# 04-AT86RF215IQ.net
KiCad netlist of a schematic drawn in Altium Designer
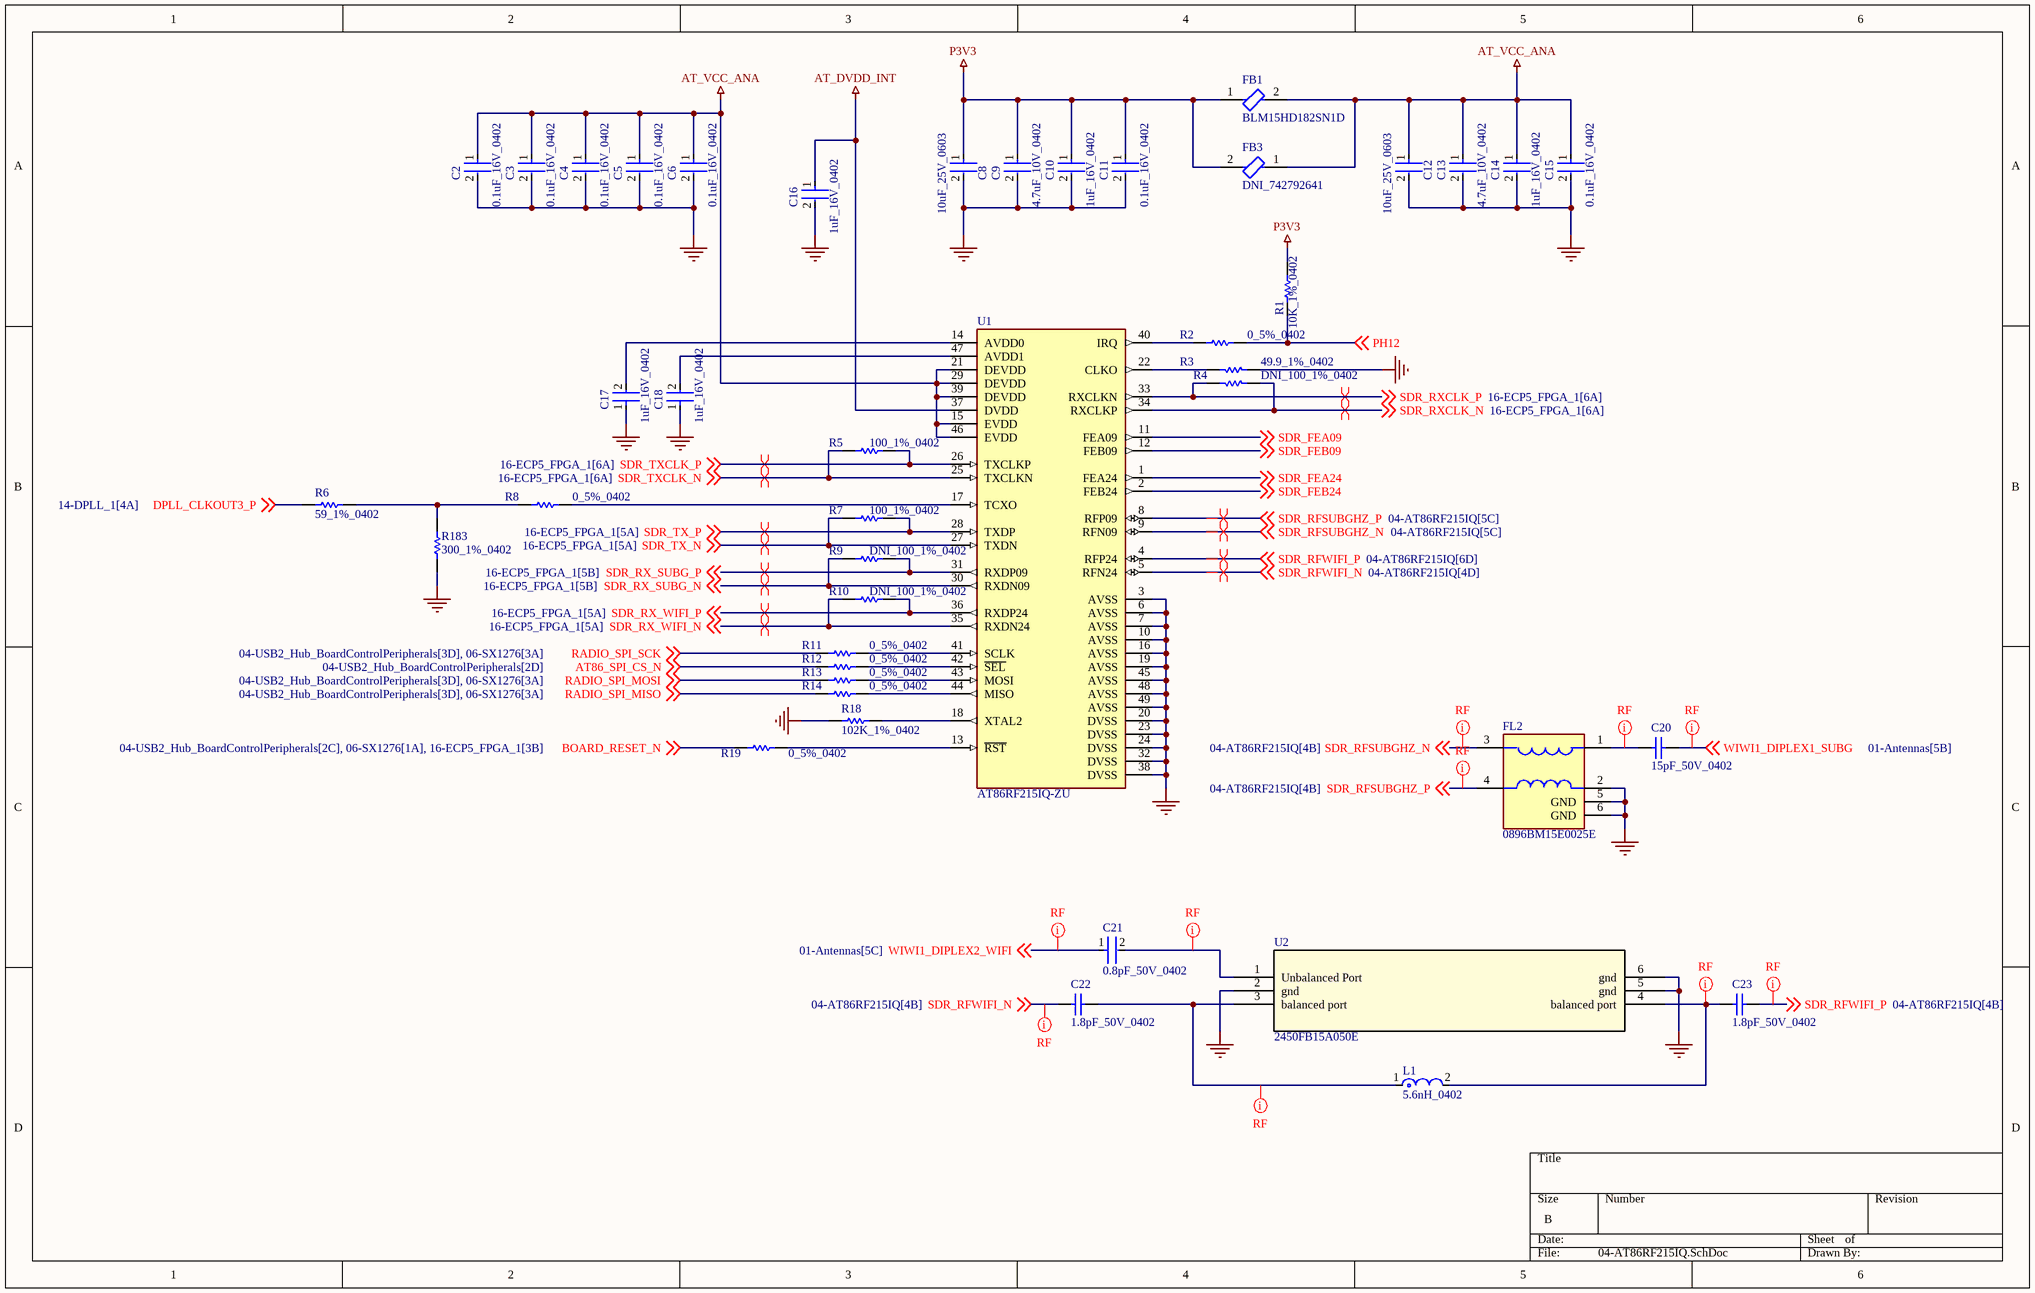
[diagram p0: 04-AT86RF215IQ.SchDoc]

(export (version "E")
  (design (tool "Eeschema 10.0.6"))
  (components
    (comp (ref "C2")
      (value "0.1uF_16V_0402")
      (footprint "FP-C0402-BB-MFG")
      (description "CAP CER 0.1UF 16V 5% X7R 0402")
      (fields
        (field (name "MANUFACTURER") "Kemet")
        (field (name "MANUFACTURER PART NUMBER") "C0402C104J4RACTU")
      )
      (libsource (lib "Altium Content Vault") (part "b4654b650e69147ec39a6b967a45e02"))
    )
    (comp (ref "C3")
      (value "0.1uF_16V_0402")
      (footprint "FP-C0402-BB-MFG")
      (description "CAP CER 0.1UF 16V 5% X7R 0402")
      (fields
        (field (name "MANUFACTURER") "Kemet")
        (field (name "MANUFACTURER PART NUMBER") "C0402C104J4RACTU")
      )
      (libsource (lib "Altium Content Vault") (part "b4654b650e69147ec39a6b967a45e02"))
    )
    (comp (ref "C4")
      (value "0.1uF_16V_0402")
      (footprint "FP-C0402-BB-MFG")
      (description "CAP CER 0.1UF 16V 5% X7R 0402")
      (fields
        (field (name "MANUFACTURER") "Kemet")
        (field (name "MANUFACTURER PART NUMBER") "C0402C104J4RACTU")
      )
      (libsource (lib "Altium Content Vault") (part "b4654b650e69147ec39a6b967a45e02"))
    )
    (comp (ref "C5")
      (value "0.1uF_16V_0402")
      (footprint "FP-C0402-BB-MFG")
      (description "CAP CER 0.1UF 16V 5% X7R 0402")
      (fields
        (field (name "MANUFACTURER") "Kemet")
        (field (name "MANUFACTURER PART NUMBER") "C0402C104J4RACTU")
      )
      (libsource (lib "Altium Content Vault") (part "b4654b650e69147ec39a6b967a45e02"))
    )
    (comp (ref "C6")
      (value "0.1uF_16V_0402")
      (footprint "FP-C0402-BB-MFG")
      (description "CAP CER 0.1UF 16V 5% X7R 0402")
      (fields
        (field (name "MANUFACTURER") "Kemet")
        (field (name "MANUFACTURER PART NUMBER") "C0402C104J4RACTU")
      )
      (libsource (lib "Altium Content Vault") (part "b4654b650e69147ec39a6b967a45e02"))
    )
    (comp (ref "C8")
      (value "10uF_25V_0603")
      (footprint "FP-CL10-IPC_C")
      (description "Cap Ceramic 10uF 25V X5R ±20% Pad SMD 0603 +85°C T/R")
      (fields (field (name "TOLERANCE") "20%"))
      (libsource (lib "Altium Content Vault") (part "b4654b650e69147ec39a6b967a45e02"))
    )
    (comp (ref "C9")
      (value "4.7uF_10V_0402")
      (footprint "FP-C1005-050-0_15-MFG")
      (description "CAP CER 4.7UF 10V X5R 0402")
      (fields (field (name "TOLERANCE") "10%"))
      (libsource (lib "Altium Content Vault") (part "b4654b650e69147ec39a6b967a45e02"))
    )
    (comp (ref "C10")
      (value "1uF_16V_0402")
      (footprint "FP-0402-L_1_0_0_05-W_0_5-IPC_A")
      (description "None")
      (fields (field (name "TOLERANCE") "10%"))
      (libsource (lib "Altium Content Vault") (part "b4654b650e69147ec39a6b967a45e02"))
    )
    (comp (ref "C11")
      (value "0.1uF_16V_0402")
      (footprint "FP-C0402-BB-MFG")
      (description "CAP CER 0.1UF 16V 5% X7R 0402")
      (fields
        (field (name "MANUFACTURER") "Kemet")
        (field (name "MANUFACTURER PART NUMBER") "C0402C104J4RACTU")
      )
      (libsource (lib "Altium Content Vault") (part "b4654b650e69147ec39a6b967a45e02"))
    )
    (comp (ref "C12")
      (value "10uF_25V_0603")
      (footprint "FP-CL10-IPC_C")
      (description "Cap Ceramic 10uF 25V X5R ±20% Pad SMD 0603 +85°C T/R")
      (fields (field (name "TOLERANCE") "20%"))
      (libsource (lib "Altium Content Vault") (part "b4654b650e69147ec39a6b967a45e02"))
    )
    (comp (ref "C13")
      (value "4.7uF_10V_0402")
      (footprint "FP-C1005-050-0_15-MFG")
      (description "CAP CER 4.7UF 10V X5R 0402")
      (fields (field (name "TOLERANCE") "10%"))
      (libsource (lib "Altium Content Vault") (part "b4654b650e69147ec39a6b967a45e02"))
    )
    (comp (ref "C14")
      (value "1uF_16V_0402")
      (footprint "FP-0402-L_1_0_0_05-W_0_5-IPC_A")
      (description "None")
      (fields (field (name "TOLERANCE") "10%"))
      (libsource (lib "Altium Content Vault") (part "b4654b650e69147ec39a6b967a45e02"))
    )
    (comp (ref "C15")
      (value "0.1uF_16V_0402")
      (footprint "FP-C0402-BB-MFG")
      (description "CAP CER 0.1UF 16V 5% X7R 0402")
      (fields
        (field (name "MANUFACTURER") "Kemet")
        (field (name "MANUFACTURER PART NUMBER") "C0402C104J4RACTU")
      )
      (libsource (lib "Altium Content Vault") (part "b4654b650e69147ec39a6b967a45e02"))
    )
    (comp (ref "C16")
      (value "1uF_16V_0402")
      (footprint "FP-0402-L_1_0_0_05-W_0_5-IPC_A")
      (description "None")
      (fields (field (name "TOLERANCE") "10%"))
      (libsource (lib "Altium Content Vault") (part "b4654b650e69147ec39a6b967a45e02"))
    )
    (comp (ref "C17")
      (value "1uF_16V_0402")
      (footprint "FP-0402-L_1_0_0_05-W_0_5-IPC_A")
      (description "None")
      (fields (field (name "TOLERANCE") "10%"))
      (libsource (lib "Altium Content Vault") (part "b4654b650e69147ec39a6b967a45e02"))
    )
    (comp (ref "C18")
      (value "1uF_16V_0402")
      (footprint "FP-0402-L_1_0_0_05-W_0_5-IPC_A")
      (description "None")
      (fields (field (name "TOLERANCE") "10%"))
      (libsource (lib "Altium Content Vault") (part "b4654b650e69147ec39a6b967a45e02"))
    )
    (comp (ref "C20")
      (value "15pF_50V_0402")
      (footprint "CAPC1005X55X25NL05T10")
      (fields (field (name "PART NUMBER") "GRM1555C1H150JZ01D") (field (name "MANUFACTURER") "Murata"))
      (libsource (lib "Altium Content Vault") (part "CAP"))
    )
    (comp (ref "C21")
      (value "0.8pF_50V_0402")
      (footprint "FP-GJM155-0_05-IPC_A")
      (description "Multi-Layer Ceramic Capacitor 0.8pF C0G  ±0.1pF 0402 Paper T/R")
      (fields (field (name "VOLTAGE") "50V"))
      (libsource (lib "Altium Content Vault") (part "02cd4be3c70576c341d710602a673aa"))
    )
    (comp (ref "C22")
      (value "1.8pF_50V_0402")
      (footprint "CAPC1005X55X25LL05T10")
      (fields (field (name "PART NUMBER") "GRM1555C1H1R8CA01D") (field (name "MANUFACTURER") "Murata"))
      (libsource (lib "Altium Content Vault") (part "CAP"))
    )
    (comp (ref "C23")
      (value "1.8pF_50V_0402")
      (footprint "CAPC1005X55X25LL05T10")
      (fields (field (name "PART NUMBER") "GRM1555C1H1R8CA01D") (field (name "MANUFACTURER") "Murata"))
      (libsource (lib "Altium Content Vault") (part "CAP"))
    )
    (comp (ref "FB1")
      (value "BLM15HD182SN1D")
      (footprint "FP-BLM15-0_05-MFG")
      (description "Chip Ferrite Bead, 0402, 1800Ω @ 100MHz, 2.2Ω, 25%, 200mA")
      (fields (field (name "TOLERANCE") "25%"))
      (libsource (lib "Altium Content Vault") (part "5f30dd21d616792df468990f7003faa"))
    )
    (comp (ref "FB3")
      (value "DNI_742792641")
      (footprint "FP-742792641-MFG")
      (description "FERRITE BEAD 300 OHM 0603 1LN")
      (fields (field (name "TOLERANCE") "25%"))
      (libsource (lib "Altium Content Vault") (part "5f30dd21d616792df468990f7003faa"))
    )
    (comp (ref "FL2")
      (value "0896BM15E0025E")
      (footprint "FP-0896BM15E0025E-MFG")
      (description "BALUN 863MHZ-928MHZ 50/50 0805")
      (fields
        (field (name "MANUFACTURER") "Johanson")
        (field (name "OCTOPART") "https://octopart.com/0896bm15e0025e-johanson-71691697")
      )
      (libsource (lib "Altium Content Vault") (part "9725e6fc3b6d4b71249fb6cd7b91a1d"))
    )
    (comp (ref "L1")
      (value "5.6nH_0402")
      (footprint "FP-LQG15HH_02-IPC_A")
      (description "Multilayer type RF Inductor 5.6nH ±0.3nH 0.18Ω 600mA 0402")
      (libsource (lib "Altium Content Vault") (part "4cc4b267dca4c8e51f7102f422741d8"))
    )
    (comp (ref "R1")
      (value "10K_1%_0402")
      (footprint "RESC1005X40X25NL10T10")
      (fields (field (name "MANUFACTURER") "Bourns") (field (name "PART NUMBER") "CR0402-FX-1002GLF"))
      (libsource (lib "Altium Content Vault") (part "RES"))
    )
    (comp (ref "R2")
      (value "0_5%_0402")
      (footprint "RESC1005X40X25NL05T10")
      (fields (field (name "MANUFACTURER") "Panasonic") (field (name "PART NUMBER") "ERJ-U020R00X"))
      (libsource (lib "Altium Content Vault") (part "RES"))
    )
    (comp (ref "R3")
      (value "49.9_1%_0402")
      (footprint "RESC1005X40X25NL10T10")
      (fields (field (name "PART NUMBER") "RK73H1ETTP49R9F") (field (name "MANUFACTURER") "KOA Speer"))
      (libsource (lib "Altium Content Vault") (part "RES"))
    )
    (comp (ref "R4")
      (value "DNI_100_1%_0402")
      (footprint "RESC1005X40X25NL05T10")
      (fields (field (name "MANUFACTURER") "Yageo") (field (name "PART NUMBER") "RC0402FR-13100RL"))
      (libsource (lib "Altium Content Vault") (part "RES"))
    )
    (comp (ref "R5")
      (value "100_1%_0402")
      (footprint "RESC1005X40X25NL05T10")
      (fields (field (name "MANUFACTURER") "Yageo") (field (name "PART NUMBER") "RC0402FR-13100RL"))
      (libsource (lib "Altium Content Vault") (part "RES"))
    )
    (comp (ref "R6")
      (value "59_1%_0402")
      (footprint "RESC1005X40X25ML10T10")
      (fields (field (name "MANUFACTURER") "KOA Speer") (field (name "PART NUMBER") "RK73H1ETTP59R0F"))
      (libsource (lib "Altium Content Vault") (part "RES"))
    )
    (comp (ref "R7")
      (value "100_1%_0402")
      (footprint "RESC1005X40X25NL05T10")
      (fields (field (name "MANUFACTURER") "Yageo") (field (name "PART NUMBER") "RC0402FR-13100RL"))
      (libsource (lib "Altium Content Vault") (part "RES"))
    )
    (comp (ref "R8")
      (value "0_5%_0402")
      (footprint "RESC1005X40X25NL05T10")
      (fields (field (name "MANUFACTURER") "Panasonic") (field (name "PART NUMBER") "ERJ-U020R00X"))
      (libsource (lib "Altium Content Vault") (part "RES"))
    )
    (comp (ref "R9")
      (value "DNI_100_1%_0402")
      (footprint "RESC1005X40X25NL05T10")
      (fields (field (name "MANUFACTURER") "Yageo") (field (name "PART NUMBER") "RC0402FR-13100RL"))
      (libsource (lib "Altium Content Vault") (part "RES"))
    )
    (comp (ref "R10")
      (value "DNI_100_1%_0402")
      (footprint "RESC1005X40X25NL05T10")
      (fields (field (name "MANUFACTURER") "Yageo") (field (name "PART NUMBER") "RC0402FR-13100RL"))
      (libsource (lib "Altium Content Vault") (part "RES"))
    )
    (comp (ref "R11")
      (value "0_5%_0402")
      (footprint "RESC1005X40X25NL05T10")
      (fields (field (name "MANUFACTURER") "Panasonic") (field (name "PART NUMBER") "ERJ-U020R00X"))
      (libsource (lib "Altium Content Vault") (part "RES"))
    )
    (comp (ref "R12")
      (value "0_5%_0402")
      (footprint "RESC1005X40X25NL05T10")
      (fields (field (name "MANUFACTURER") "Panasonic") (field (name "PART NUMBER") "ERJ-U020R00X"))
      (libsource (lib "Altium Content Vault") (part "RES"))
    )
    (comp (ref "R13")
      (value "0_5%_0402")
      (footprint "RESC1005X40X25NL05T10")
      (fields (field (name "MANUFACTURER") "Panasonic") (field (name "PART NUMBER") "ERJ-U020R00X"))
      (libsource (lib "Altium Content Vault") (part "RES"))
    )
    (comp (ref "R14")
      (value "0_5%_0402")
      (footprint "RESC1005X40X25NL05T10")
      (fields (field (name "MANUFACTURER") "Panasonic") (field (name "PART NUMBER") "ERJ-U020R00X"))
      (libsource (lib "Altium Content Vault") (part "RES"))
    )
    (comp (ref "R18")
      (value "102K_1%_0402")
      (footprint "RESC1005X40X25ML05T10")
      (fields (field (name "MANUFACTURER") "Yageo") (field (name "PART NUMBER") "RC0402FR-07102KL"))
      (libsource (lib "Altium Content Vault") (part "RES"))
    )
    (comp (ref "R19")
      (value "0_5%_0402")
      (footprint "RESC1005X40X25NL05T10")
      (fields (field (name "MANUFACTURER") "Panasonic") (field (name "PART NUMBER") "ERJ-U020R00X"))
      (libsource (lib "Altium Content Vault") (part "RES"))
    )
    (comp (ref "R183")
      (value "300_1%_0402")
      (footprint "RESC1005X40X25LL10T10")
      (fields (field (name "PART NUMBER") "MC00625W04021300R") (field (name "MANUFACTURER") "Multicomp"))
      (libsource (lib "Altium Content Vault") (part "RES"))
    )
    (comp (ref "U1")
      (value "AT86RF215IQ-ZU")
      (footprint "FP-AT86RF215IQ-ZU-MFG")
      (description "IC RF TXRX 802.15.4 48VFQFN")
      (fields
        (field (name "MANUFACTURER") "Microchip")
        (field (name "OCTOPART") "https://octopart.com/at86rf215iq-zu-microchip-77758620")
      )
      (libsource (lib "Altium Content Vault") (part "c531c0ad6565c2a43c7312791734b45"))
    )
    (comp (ref "U2")
      (value "2450FB15A050E")
      (footprint "2450FB15A050E_JOT")
      (description "No Description Available")
      (libsource (lib "2450FB15A050E") (part "2450FB15A050E"))
    )
  )
  (nets
    (net (code "1") (name "AT86_SPI_CS_N") (class "Default")
      (node (ref "R12") (pin "1") (pinfunction "1_1") (pintype "passive"))
    )
    (net (code "2") (name "AT_DVDD_INT") (class "Default")
      (node (ref "C16") (pin "1") (pinfunction "1_1") (pintype "passive"))
      (node (ref "U1") (pin "37") (pinfunction "DVDD_37") (pintype "power_in"))
    )
    (net (code "3") (name "AT_VCC_ANA") (class "Default")
      (node (ref "C12") (pin "1") (pinfunction "1_1") (pintype "passive"))
      (node (ref "C13") (pin "1") (pinfunction "1_1") (pintype "passive"))
      (node (ref "C14") (pin "1") (pinfunction "1_1") (pintype "passive"))
      (node (ref "C15") (pin "1") (pinfunction "1_1") (pintype "passive"))
      (node (ref "C2") (pin "1") (pinfunction "1_1") (pintype "passive"))
      (node (ref "C3") (pin "1") (pinfunction "1_1") (pintype "passive"))
      (node (ref "C4") (pin "1") (pinfunction "1_1") (pintype "passive"))
      (node (ref "C5") (pin "1") (pinfunction "1_1") (pintype "passive"))
      (node (ref "C6") (pin "1") (pinfunction "1_1") (pintype "passive"))
      (node (ref "FB1") (pin "2") (pinfunction "2_2") (pintype "passive"))
      (node (ref "FB3") (pin "1") (pinfunction "1_1") (pintype "passive"))
      (node (ref "U1") (pin "15") (pinfunction "EVDD_15") (pintype "power_in"))
      (node (ref "U1") (pin "21") (pinfunction "DEVDD_21") (pintype "power_in"))
      (node (ref "U1") (pin "29") (pinfunction "DEVDD_29") (pintype "power_in"))
      (node (ref "U1") (pin "39") (pinfunction "DEVDD_39") (pintype "power_in"))
      (node (ref "U1") (pin "46") (pinfunction "EVDD_46") (pintype "power_in"))
    )
    (net (code "4") (name "BOARD_RESET_N") (class "Default")
      (node (ref "R19") (pin "1") (pinfunction "1_1") (pintype "passive"))
    )
    (net (code "5") (name "DPLL_CLKOUT3_P") (class "Default")
      (node (ref "R6") (pin "1") (pinfunction "1_1") (pintype "passive"))
    )
    (net (code "6") (name "GND") (class "Default")
      (node (ref "C10") (pin "2") (pinfunction "2_2") (pintype "passive"))
      (node (ref "C11") (pin "2") (pinfunction "2_2") (pintype "passive"))
      (node (ref "C12") (pin "2") (pinfunction "2_2") (pintype "passive"))
      (node (ref "C13") (pin "2") (pinfunction "2_2") (pintype "passive"))
      (node (ref "C14") (pin "2") (pinfunction "2_2") (pintype "passive"))
      (node (ref "C15") (pin "2") (pinfunction "2_2") (pintype "passive"))
      (node (ref "C16") (pin "2") (pinfunction "2_2") (pintype "passive"))
      (node (ref "C17") (pin "1") (pinfunction "1_1") (pintype "passive"))
      (node (ref "C18") (pin "1") (pinfunction "1_1") (pintype "passive"))
      (node (ref "C2") (pin "2") (pinfunction "2_2") (pintype "passive"))
      (node (ref "C3") (pin "2") (pinfunction "2_2") (pintype "passive"))
      (node (ref "C4") (pin "2") (pinfunction "2_2") (pintype "passive"))
      (node (ref "C5") (pin "2") (pinfunction "2_2") (pintype "passive"))
      (node (ref "C6") (pin "2") (pinfunction "2_2") (pintype "passive"))
      (node (ref "C8") (pin "2") (pinfunction "2_2") (pintype "passive"))
      (node (ref "C9") (pin "2") (pinfunction "2_2") (pintype "passive"))
      (node (ref "FL2") (pin "2") (pinfunction "GND_2") (pintype "power_in"))
      (node (ref "FL2") (pin "5") (pinfunction "GND_5") (pintype "power_in"))
      (node (ref "FL2") (pin "6") (pinfunction "GND_6") (pintype "power_in"))
      (node (ref "R18") (pin "1") (pinfunction "1_1") (pintype "passive"))
      (node (ref "R183") (pin "1") (pinfunction "1_1") (pintype "passive"))
      (node (ref "R3") (pin "2") (pinfunction "2_2") (pintype "passive"))
      (node (ref "U1") (pin "10") (pinfunction "AVSS_10") (pintype "power_in"))
      (node (ref "U1") (pin "16") (pinfunction "AVSS_16") (pintype "power_in"))
      (node (ref "U1") (pin "19") (pinfunction "AVSS_19") (pintype "power_in"))
      (node (ref "U1") (pin "20") (pinfunction "DVSS_20") (pintype "power_in"))
      (node (ref "U1") (pin "23") (pinfunction "DVSS_23") (pintype "power_in"))
      (node (ref "U1") (pin "24") (pinfunction "DVSS_24") (pintype "power_in"))
      (node (ref "U1") (pin "3") (pinfunction "AVSS_3") (pintype "power_in"))
      (node (ref "U1") (pin "32") (pinfunction "DVSS_32") (pintype "power_in"))
      (node (ref "U1") (pin "38") (pinfunction "DVSS_38") (pintype "power_in"))
      (node (ref "U1") (pin "45") (pinfunction "AVSS_45") (pintype "power_in"))
      (node (ref "U1") (pin "48") (pinfunction "AVSS_48") (pintype "power_in"))
      (node (ref "U1") (pin "49") (pinfunction "AVSS_49") (pintype "power_in"))
      (node (ref "U1") (pin "6") (pinfunction "AVSS_6") (pintype "power_in"))
      (node (ref "U1") (pin "7") (pinfunction "AVSS_7") (pintype "power_in"))
      (node (ref "U2") (pin "2") (pinfunction "gnd_2") (pintype "passive"))
      (node (ref "U2") (pin "5") (pinfunction "gnd_5") (pintype "passive"))
      (node (ref "U2") (pin "6") (pinfunction "gnd_6") (pintype "passive"))
    )
    (net (code "7") (name "Net-(C22-Pad2)") (class "Default")
      (node (ref "C22") (pin "2") (pinfunction "2_2") (pintype "passive"))
      (node (ref "L1") (pin "1") (pinfunction "1_1") (pintype "passive"))
      (node (ref "U2") (pin "3") (pinfunction "balanced_port_3") (pintype "passive"))
    )
    (net (code "8") (name "Net-(C23-Pad1)") (class "Default")
      (node (ref "C23") (pin "1") (pinfunction "1_1") (pintype "passive"))
      (node (ref "L1") (pin "2") (pinfunction "2_2") (pintype "passive"))
      (node (ref "U2") (pin "4") (pinfunction "balanced_port_4") (pintype "passive"))
    )
    (net (code "9") (name "Net-(FL2-Unbalanced_Port)") (class "Default")
      (node (ref "C20") (pin "1") (pinfunction "1_1") (pintype "passive"))
      (node (ref "FL2") (pin "1") (pinfunction "Unbalanced_Port_1") (pintype "passive"))
    )
    (net (code "10") (name "Net-(R183-Pad2)") (class "Default")
      (node (ref "R183") (pin "2") (pinfunction "2_2") (pintype "passive"))
      (node (ref "R6") (pin "2") (pinfunction "2_2") (pintype "passive"))
      (node (ref "R8") (pin "1") (pinfunction "1_1") (pintype "passive"))
    )
    (net (code "11") (name "Net-(U1-AVDD0)") (class "Default")
      (node (ref "C17") (pin "2") (pinfunction "2_2") (pintype "passive"))
      (node (ref "U1") (pin "14") (pinfunction "AVDD0_14") (pintype "power_in"))
    )
    (net (code "12") (name "Net-(U1-AVDD1)") (class "Default")
      (node (ref "C18") (pin "2") (pinfunction "2_2") (pintype "passive"))
      (node (ref "U1") (pin "47") (pinfunction "AVDD1_47") (pintype "power_in"))
    )
    (net (code "13") (name "Net-(U1-CLKO)") (class "Default")
      (node (ref "R3") (pin "1") (pinfunction "1_1") (pintype "passive"))
      (node (ref "U1") (pin "22") (pinfunction "CLKO_22") (pintype "output"))
    )
    (net (code "14") (name "Net-(U1-IRQ)") (class "Default")
      (node (ref "R2") (pin "1") (pinfunction "1_1") (pintype "passive"))
      (node (ref "U1") (pin "40") (pinfunction "IRQ_40") (pintype "output"))
    )
    (net (code "15") (name "Net-(U1-MISO)") (class "Default")
      (node (ref "R14") (pin "2") (pinfunction "2_2") (pintype "passive"))
      (node (ref "U1") (pin "44") (pinfunction "MISO_44") (pintype "output"))
    )
    (net (code "16") (name "Net-(U1-MOSI)") (class "Default")
      (node (ref "R13") (pin "2") (pinfunction "2_2") (pintype "passive"))
      (node (ref "U1") (pin "43") (pinfunction "MOSI_43") (pintype "input"))
    )
    (net (code "17") (name "Net-(U1-SCLK)") (class "Default")
      (node (ref "R11") (pin "2") (pinfunction "2_2") (pintype "passive"))
      (node (ref "U1") (pin "41") (pinfunction "SCLK_41") (pintype "input"))
    )
    (net (code "18") (name "Net-(U1-TCXO)") (class "Default")
      (node (ref "R8") (pin "2") (pinfunction "2_2") (pintype "passive"))
      (node (ref "U1") (pin "17") (pinfunction "TCXO_17") (pintype "input"))
    )
    (net (code "19") (name "Net-(U1-XTAL2)") (class "Default")
      (node (ref "R18") (pin "2") (pinfunction "2_2") (pintype "passive"))
      (node (ref "U1") (pin "18") (pinfunction "XTAL2_18") (pintype "output"))
    )
    (net (code "20") (name "Net-(U1-~{RST})") (class "Default")
      (node (ref "R19") (pin "2") (pinfunction "2_2") (pintype "passive"))
      (node (ref "U1") (pin "13") (pinfunction "~{RST}_13") (pintype "input"))
    )
    (net (code "21") (name "Net-(U1-~{SEL})") (class "Default")
      (node (ref "R12") (pin "2") (pinfunction "2_2") (pintype "passive"))
      (node (ref "U1") (pin "42") (pinfunction "~{SEL}_42") (pintype "input"))
    )
    (net (code "22") (name "Net-(U2-Unbalanced_Port)") (class "Default")
      (node (ref "C21") (pin "2") (pinfunction "2_2") (pintype "passive"))
      (node (ref "U2") (pin "1") (pinfunction "Unbalanced_Port_1") (pintype "passive"))
    )
    (net (code "23") (name "P3V3") (class "Default")
      (node (ref "C10") (pin "1") (pinfunction "1_1") (pintype "passive"))
      (node (ref "C11") (pin "1") (pinfunction "1_1") (pintype "passive"))
      (node (ref "C8") (pin "1") (pinfunction "1_1") (pintype "passive"))
      (node (ref "C9") (pin "1") (pinfunction "1_1") (pintype "passive"))
      (node (ref "FB1") (pin "1") (pinfunction "1_1") (pintype "passive"))
      (node (ref "FB3") (pin "2") (pinfunction "2_2") (pintype "passive"))
      (node (ref "R1") (pin "2") (pinfunction "2_2") (pintype "passive"))
    )
    (net (code "24") (name "PH12") (class "Default")
      (node (ref "R1") (pin "1") (pinfunction "1_1") (pintype "passive"))
      (node (ref "R2") (pin "2") (pinfunction "2_2") (pintype "passive"))
    )
    (net (code "25") (name "RADIO_SPI_MISO") (class "Default")
      (node (ref "R14") (pin "1") (pinfunction "1_1") (pintype "passive"))
    )
    (net (code "26") (name "RADIO_SPI_MOSI") (class "Default")
      (node (ref "R13") (pin "1") (pinfunction "1_1") (pintype "passive"))
    )
    (net (code "27") (name "RADIO_SPI_SCK") (class "Default")
      (node (ref "R11") (pin "1") (pinfunction "1_1") (pintype "passive"))
    )
    (net (code "28") (name "SDR_FEA09") (class "Default")
      (node (ref "U1") (pin "11") (pinfunction "FEA09_11") (pintype "output"))
    )
    (net (code "29") (name "SDR_FEA24") (class "Default")
      (node (ref "U1") (pin "1") (pinfunction "FEA24_1") (pintype "output"))
    )
    (net (code "30") (name "SDR_FEB09") (class "Default")
      (node (ref "U1") (pin "12") (pinfunction "FEB09_12") (pintype "output"))
    )
    (net (code "31") (name "SDR_FEB24") (class "Default")
      (node (ref "U1") (pin "2") (pinfunction "FEB24_2") (pintype "output"))
    )
    (net (code "32") (name "SDR_RFSUBGHZ_N") (class "Default")
      (node (ref "FL2") (pin "3") (pinfunction "1_Balanced_Port_3") (pintype "passive"))
      (node (ref "U1") (pin "9") (pinfunction "RFN09_9") (pintype "bidirectional"))
    )
    (net (code "33") (name "SDR_RFSUBGHZ_P") (class "Default")
      (node (ref "FL2") (pin "4") (pinfunction "2_Balanced_Port_4") (pintype "passive"))
      (node (ref "U1") (pin "8") (pinfunction "RFP09_8") (pintype "bidirectional"))
    )
    (net (code "34") (name "SDR_RFWIFI_N") (class "Default")
      (node (ref "C22") (pin "1") (pinfunction "1_1") (pintype "passive"))
      (node (ref "U1") (pin "5") (pinfunction "RFN24_5") (pintype "bidirectional"))
    )
    (net (code "35") (name "SDR_RFWIFI_P") (class "Default")
      (node (ref "C23") (pin "2") (pinfunction "2_2") (pintype "passive"))
      (node (ref "U1") (pin "4") (pinfunction "RFP24_4") (pintype "bidirectional"))
    )
    (net (code "36") (name "SDR_RXCLK_N") (class "Default")
      (node (ref "R4") (pin "1") (pinfunction "1_1") (pintype "passive"))
      (node (ref "U1") (pin "34") (pinfunction "RXCLKP_34") (pintype "output"))
    )
    (net (code "37") (name "SDR_RXCLK_P") (class "Default")
      (node (ref "R4") (pin "2") (pinfunction "2_2") (pintype "passive"))
      (node (ref "U1") (pin "33") (pinfunction "RXCLKN_33") (pintype "output"))
    )
    (net (code "38") (name "SDR_RX_SUBG_N") (class "Default")
      (node (ref "R9") (pin "1") (pinfunction "1_1") (pintype "passive"))
      (node (ref "U1") (pin "30") (pinfunction "RXDN09_30") (pintype "output"))
    )
    (net (code "39") (name "SDR_RX_SUBG_P") (class "Default")
      (node (ref "R9") (pin "2") (pinfunction "2_2") (pintype "passive"))
      (node (ref "U1") (pin "31") (pinfunction "RXDP09_31") (pintype "output"))
    )
    (net (code "40") (name "SDR_RX_WIFI_N") (class "Default")
      (node (ref "R10") (pin "1") (pinfunction "1_1") (pintype "passive"))
      (node (ref "U1") (pin "35") (pinfunction "RXDN24_35") (pintype "output"))
    )
    (net (code "41") (name "SDR_RX_WIFI_P") (class "Default")
      (node (ref "R10") (pin "2") (pinfunction "2_2") (pintype "passive"))
      (node (ref "U1") (pin "36") (pinfunction "RXDP24_36") (pintype "output"))
    )
    (net (code "42") (name "SDR_TXCLK_N") (class "Default")
      (node (ref "R5") (pin "1") (pinfunction "1_1") (pintype "passive"))
      (node (ref "U1") (pin "25") (pinfunction "TXCLKN_25") (pintype "input"))
    )
    (net (code "43") (name "SDR_TXCLK_P") (class "Default")
      (node (ref "R5") (pin "2") (pinfunction "2_2") (pintype "passive"))
      (node (ref "U1") (pin "26") (pinfunction "TXCLKP_26") (pintype "input"))
    )
    (net (code "44") (name "SDR_TX_N") (class "Default")
      (node (ref "R7") (pin "1") (pinfunction "1_1") (pintype "passive"))
      (node (ref "U1") (pin "27") (pinfunction "TXDN_27") (pintype "input"))
    )
    (net (code "45") (name "SDR_TX_P") (class "Default")
      (node (ref "R7") (pin "2") (pinfunction "2_2") (pintype "passive"))
      (node (ref "U1") (pin "28") (pinfunction "TXDP_28") (pintype "input"))
    )
    (net (code "46") (name "WIWI1_DIPLEX1_SUBG") (class "Default")
      (node (ref "C20") (pin "2") (pinfunction "2_2") (pintype "passive"))
    )
    (net (code "47") (name "WIWI1_DIPLEX2_WIFI") (class "Default")
      (node (ref "C21") (pin "1") (pinfunction "1_1") (pintype "passive"))
    )
  )
)
